# amplifier4c.net
KiCad netlist of a schematic drawn in EAGLE
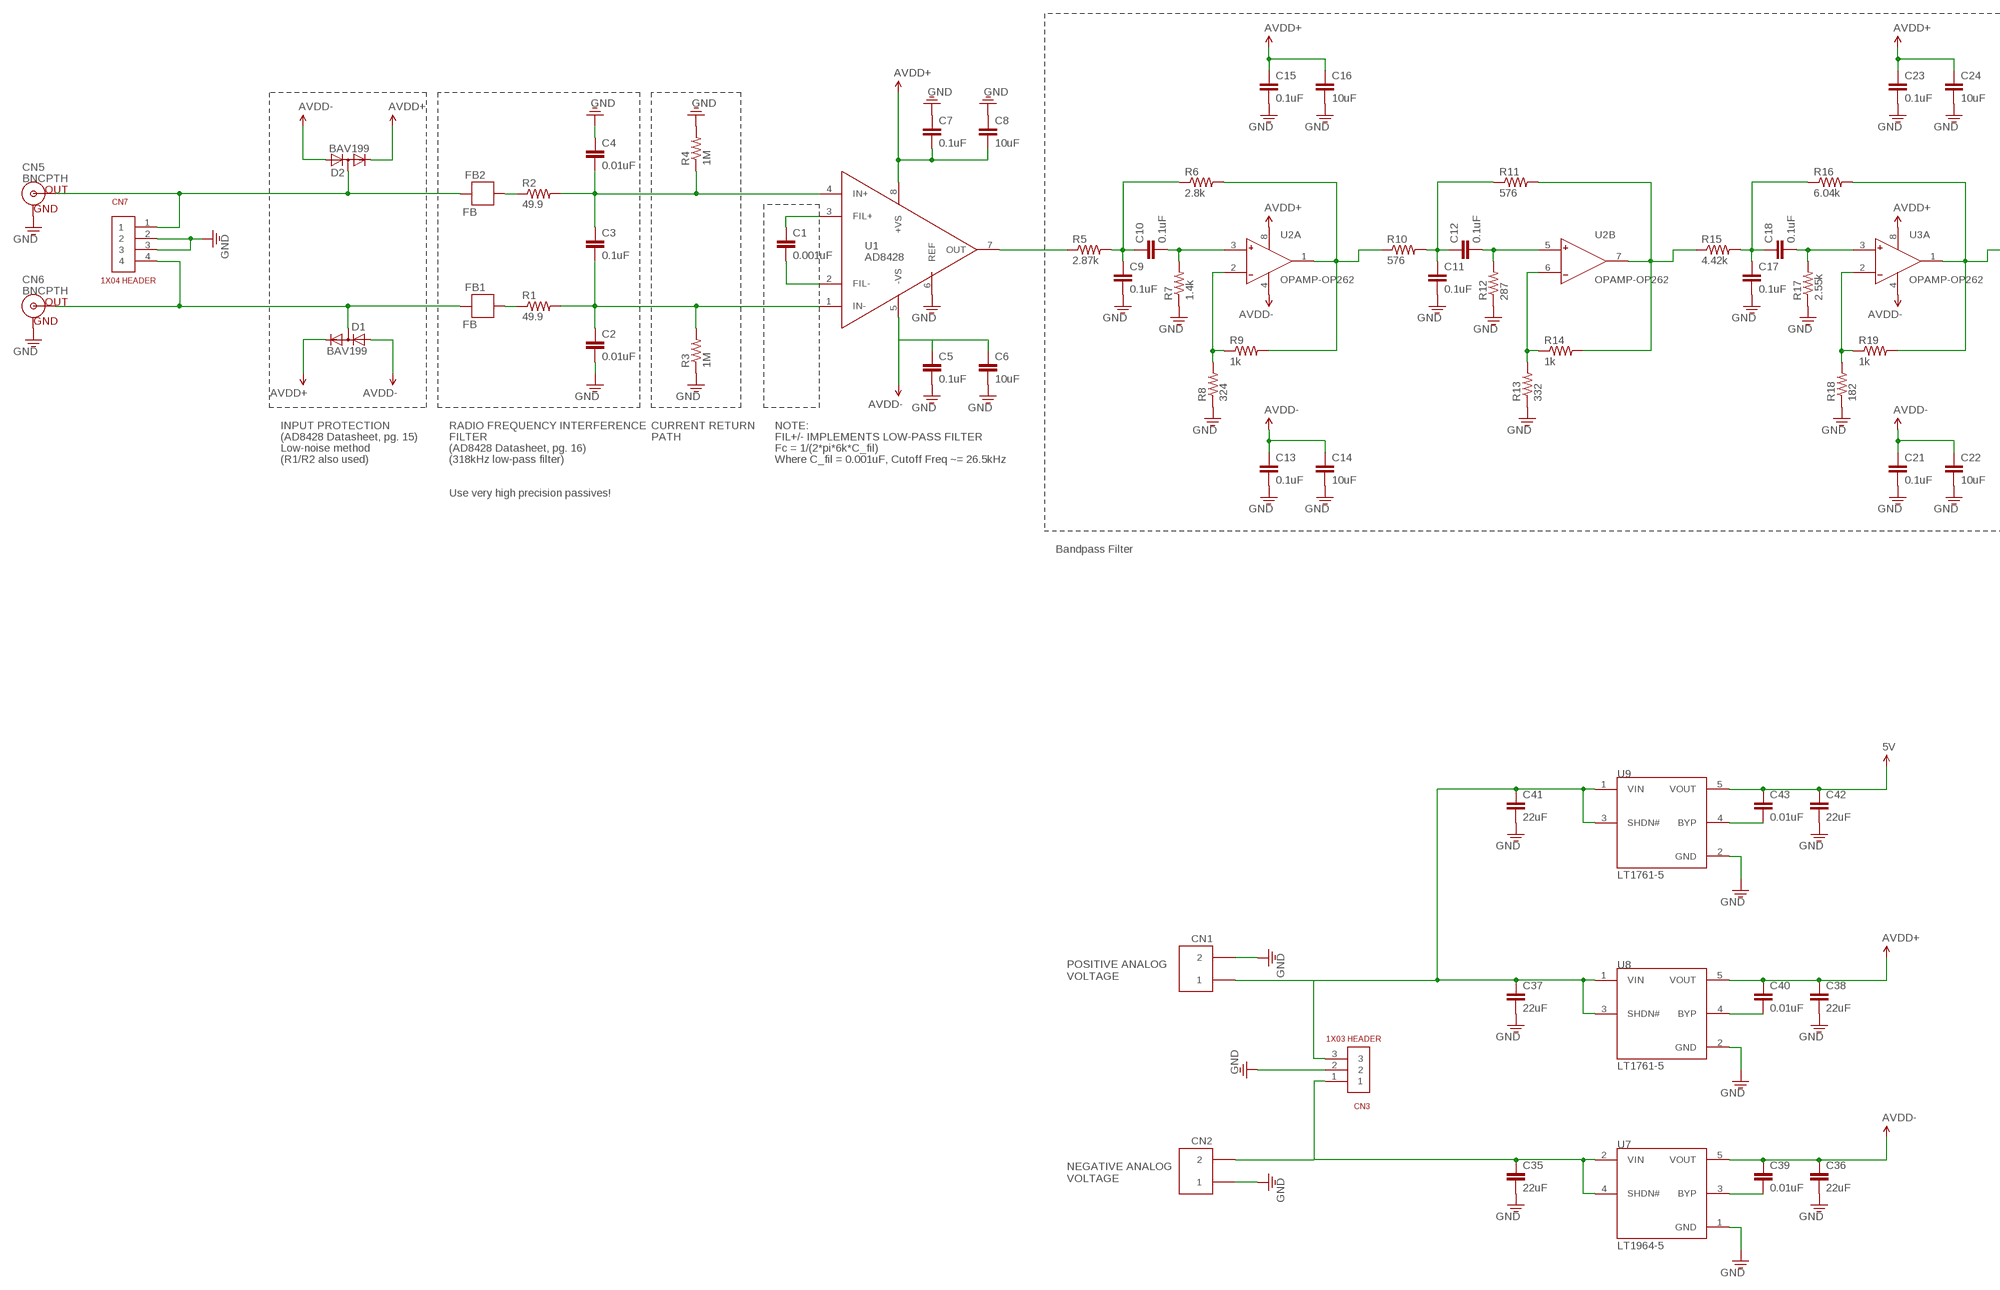
[diagram p0: schematic, sheet 1, part 1 of 2]
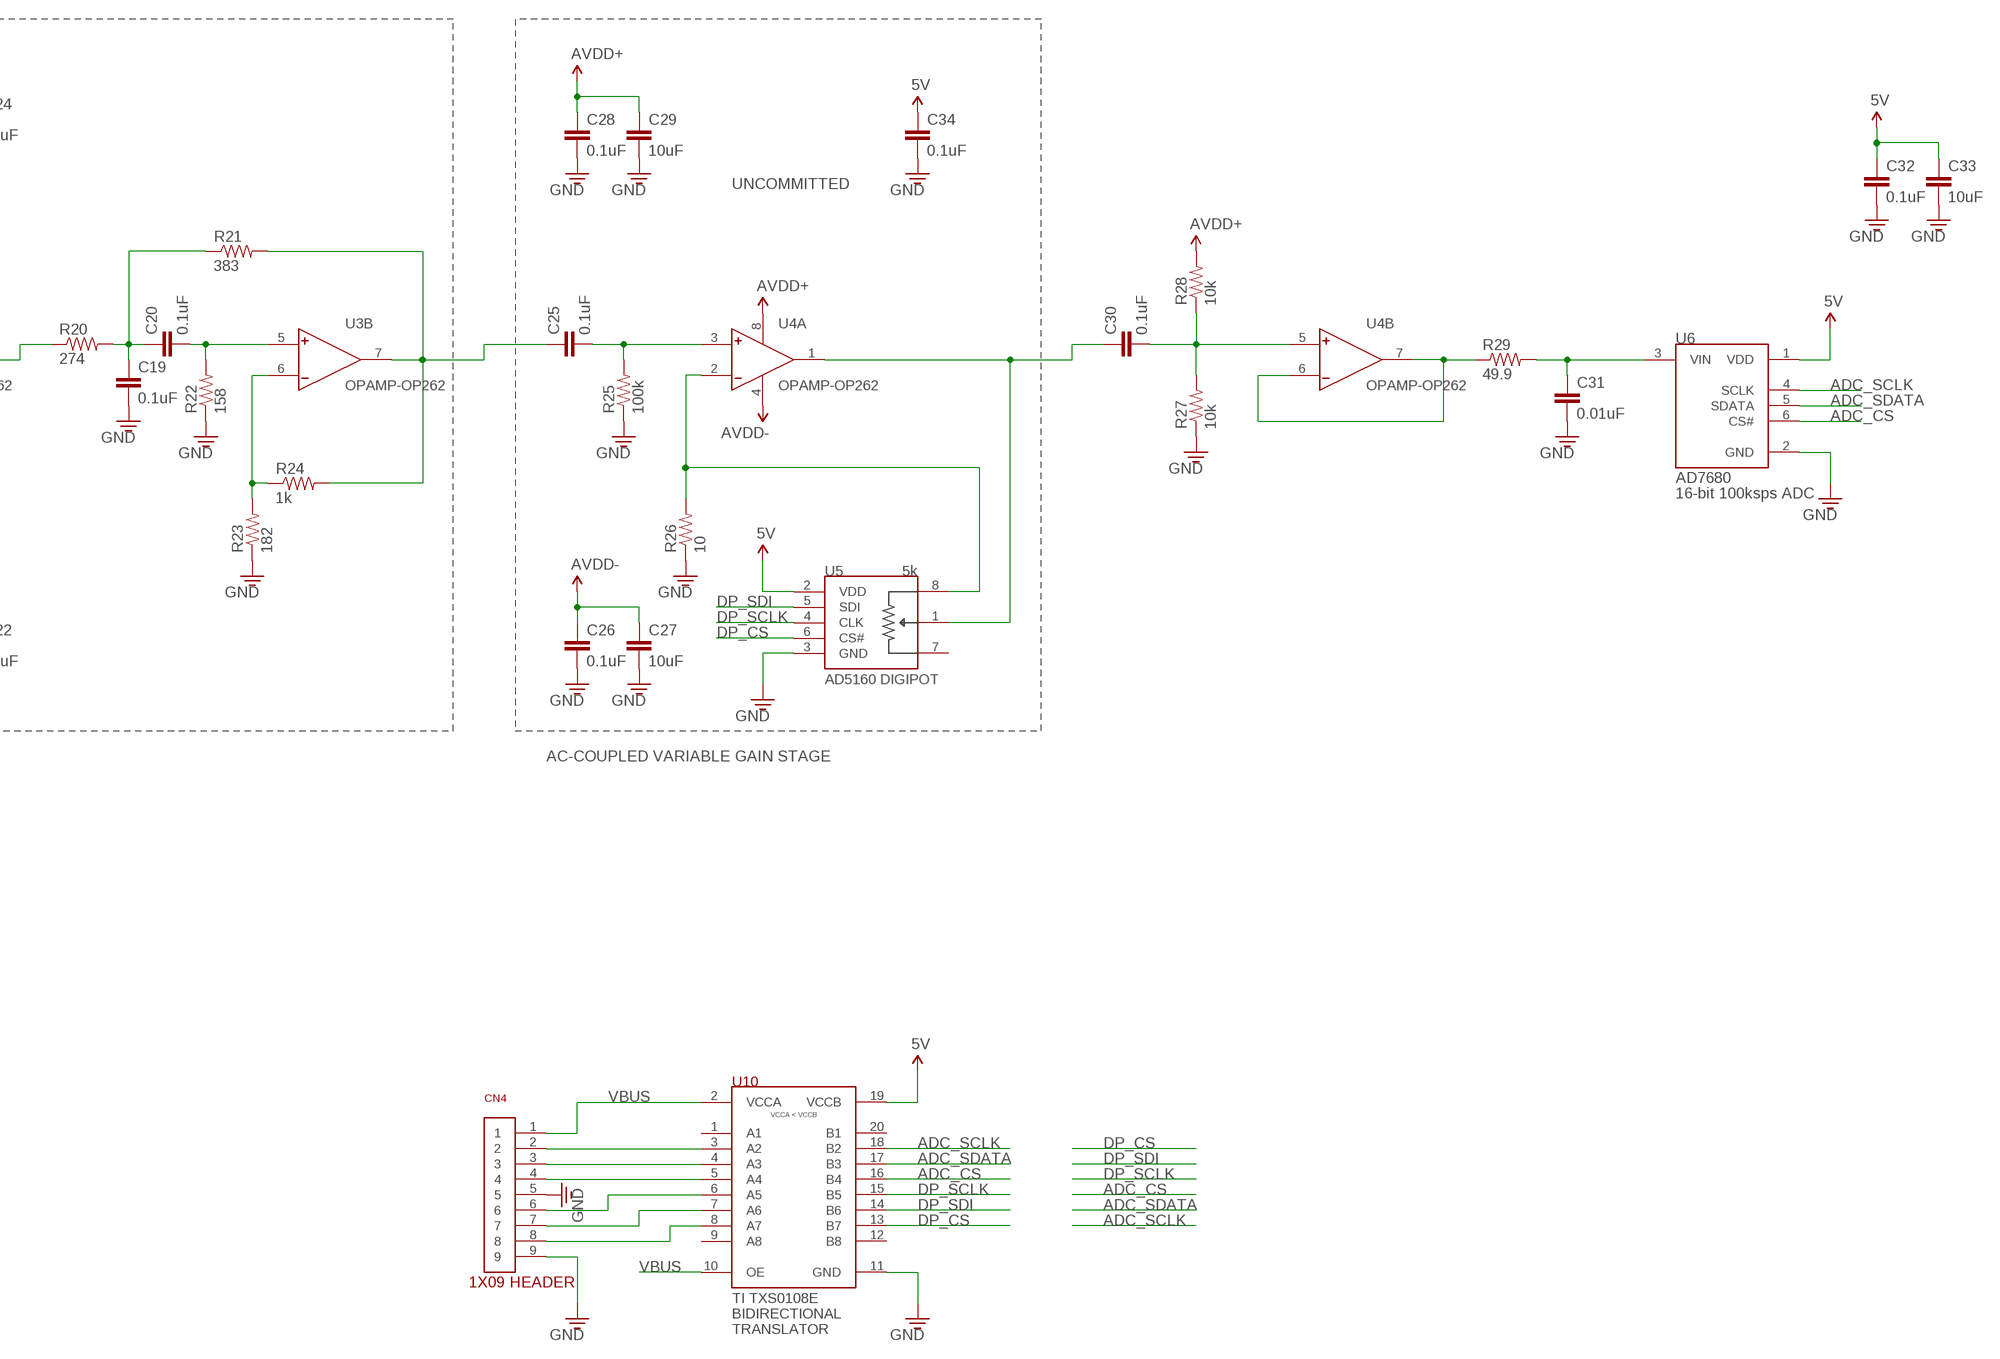
[diagram p1: schematic, sheet 1, part 2 of 2]

(export (version "E")
  (design (tool "Eeschema 10.0.6"))
  (components
    (comp (ref "C1")
      (value "0.001uF")
      (footprint "eagle-import:0603")
      (libsource (lib "eagle-import") (part "CAP0603"))
    )
    (comp (ref "C2")
      (value "0.01uF")
      (footprint "eagle-import:0603")
      (libsource (lib "eagle-import") (part "CAP0603"))
    )
    (comp (ref "C3")
      (value "0.1uF")
      (footprint "eagle-import:0603")
      (libsource (lib "eagle-import") (part "CAP0603"))
    )
    (comp (ref "C4")
      (value "0.01uF")
      (footprint "eagle-import:0603")
      (libsource (lib "eagle-import") (part "CAP0603"))
    )
    (comp (ref "C5")
      (value "0.1uF")
      (footprint "eagle-import:0603")
      (libsource (lib "eagle-import") (part "CAP0603"))
    )
    (comp (ref "C6")
      (value "10uF")
      (footprint "eagle-import:0805")
      (libsource (lib "eagle-import") (part "lowfieldmri_CAP0805"))
    )
    (comp (ref "C7")
      (value "0.1uF")
      (footprint "eagle-import:0603")
      (libsource (lib "eagle-import") (part "CAP0603"))
    )
    (comp (ref "C8")
      (value "10uF")
      (footprint "eagle-import:0805")
      (libsource (lib "eagle-import") (part "lowfieldmri_CAP0805"))
    )
    (comp (ref "C9")
      (value "0.1uF")
      (footprint "eagle-import:0603")
      (libsource (lib "eagle-import") (part "CAP0603"))
    )
    (comp (ref "C10")
      (value "0.1uF")
      (footprint "eagle-import:0603")
      (libsource (lib "eagle-import") (part "CAP0603"))
    )
    (comp (ref "C11")
      (value "0.1uF")
      (footprint "eagle-import:0603")
      (libsource (lib "eagle-import") (part "CAP0603"))
    )
    (comp (ref "C12")
      (value "0.1uF")
      (footprint "eagle-import:0603")
      (libsource (lib "eagle-import") (part "CAP0603"))
    )
    (comp (ref "C13")
      (value "0.1uF")
      (footprint "eagle-import:0603")
      (libsource (lib "eagle-import") (part "CAP0603"))
    )
    (comp (ref "C14")
      (value "10uF")
      (footprint "eagle-import:0805")
      (libsource (lib "eagle-import") (part "lowfieldmri_CAP0805"))
    )
    (comp (ref "C15")
      (value "0.1uF")
      (footprint "eagle-import:0603")
      (libsource (lib "eagle-import") (part "CAP0603"))
    )
    (comp (ref "C16")
      (value "10uF")
      (footprint "eagle-import:0805")
      (libsource (lib "eagle-import") (part "lowfieldmri_CAP0805"))
    )
    (comp (ref "C17")
      (value "0.1uF")
      (footprint "eagle-import:0603")
      (libsource (lib "eagle-import") (part "CAP0603"))
    )
    (comp (ref "C18")
      (value "0.1uF")
      (footprint "eagle-import:0603")
      (libsource (lib "eagle-import") (part "CAP0603"))
    )
    (comp (ref "C19")
      (value "0.1uF")
      (footprint "eagle-import:0603")
      (libsource (lib "eagle-import") (part "CAP0603"))
    )
    (comp (ref "C20")
      (value "0.1uF")
      (footprint "eagle-import:0603")
      (libsource (lib "eagle-import") (part "CAP0603"))
    )
    (comp (ref "C21")
      (value "0.1uF")
      (footprint "eagle-import:0603")
      (libsource (lib "eagle-import") (part "CAP0603"))
    )
    (comp (ref "C22")
      (value "10uF")
      (footprint "eagle-import:0805")
      (libsource (lib "eagle-import") (part "lowfieldmri_CAP0805"))
    )
    (comp (ref "C23")
      (value "0.1uF")
      (footprint "eagle-import:0603")
      (libsource (lib "eagle-import") (part "CAP0603"))
    )
    (comp (ref "C24")
      (value "10uF")
      (footprint "eagle-import:0805")
      (libsource (lib "eagle-import") (part "lowfieldmri_CAP0805"))
    )
    (comp (ref "C25")
      (value "0.1uF")
      (footprint "eagle-import:0603")
      (libsource (lib "eagle-import") (part "CAP0603"))
    )
    (comp (ref "C26")
      (value "0.1uF")
      (footprint "eagle-import:0603")
      (libsource (lib "eagle-import") (part "CAP0603"))
    )
    (comp (ref "C27")
      (value "10uF")
      (footprint "eagle-import:0805")
      (libsource (lib "eagle-import") (part "lowfieldmri_CAP0805"))
    )
    (comp (ref "C28")
      (value "0.1uF")
      (footprint "eagle-import:0603")
      (libsource (lib "eagle-import") (part "CAP0603"))
    )
    (comp (ref "C29")
      (value "10uF")
      (footprint "eagle-import:0805")
      (libsource (lib "eagle-import") (part "lowfieldmri_CAP0805"))
    )
    (comp (ref "C30")
      (value "0.1uF")
      (footprint "eagle-import:0603")
      (libsource (lib "eagle-import") (part "CAP0603"))
    )
    (comp (ref "C31")
      (value "0.01uF")
      (footprint "eagle-import:0603")
      (libsource (lib "eagle-import") (part "CAP0603"))
    )
    (comp (ref "C32")
      (value "0.1uF")
      (footprint "eagle-import:0603")
      (libsource (lib "eagle-import") (part "CAP0603"))
    )
    (comp (ref "C33")
      (value "10uF")
      (footprint "eagle-import:0805")
      (libsource (lib "eagle-import") (part "lowfieldmri_CAP0805"))
    )
    (comp (ref "C34")
      (value "0.1uF")
      (footprint "eagle-import:0603")
      (libsource (lib "eagle-import") (part "CAP0603"))
    )
    (comp (ref "C35")
      (value "22uF")
      (footprint "eagle-import:1206")
      (libsource (lib "eagle-import") (part "CAP1206"))
    )
    (comp (ref "C36")
      (value "22uF")
      (footprint "eagle-import:1206")
      (libsource (lib "eagle-import") (part "CAP1206"))
    )
    (comp (ref "C37")
      (value "22uF")
      (footprint "eagle-import:1206")
      (libsource (lib "eagle-import") (part "CAP1206"))
    )
    (comp (ref "C38")
      (value "22uF")
      (footprint "eagle-import:1206")
      (libsource (lib "eagle-import") (part "CAP1206"))
    )
    (comp (ref "C39")
      (value "0.01uF")
      (footprint "eagle-import:0603")
      (libsource (lib "eagle-import") (part "CAP0603"))
    )
    (comp (ref "C40")
      (value "0.01uF")
      (footprint "eagle-import:0603")
      (libsource (lib "eagle-import") (part "CAP0603"))
    )
    (comp (ref "C41")
      (value "22uF")
      (footprint "eagle-import:1206")
      (libsource (lib "eagle-import") (part "CAP1206"))
    )
    (comp (ref "C42")
      (value "22uF")
      (footprint "eagle-import:1206")
      (libsource (lib "eagle-import") (part "CAP1206"))
    )
    (comp (ref "C43")
      (value "0.01uF")
      (footprint "eagle-import:0603")
      (libsource (lib "eagle-import") (part "CAP0603"))
    )
    (comp (ref "CN1")
      (value "SCREWTERMINAL-2PIN")
      (footprint "eagle-import:SCREWTERMINAL-2PIN")
      (libsource (lib "eagle-import") (part "SCREWTERMINAL-2PIN"))
    )
    (comp (ref "CN2")
      (value "SCREWTERMINAL-2PIN")
      (footprint "eagle-import:SCREWTERMINAL-2PIN")
      (libsource (lib "eagle-import") (part "SCREWTERMINAL-2PIN"))
    )
    (comp (ref "CN3")
      (value "1X03")
      (footprint "eagle-import:1X03")
      (libsource (lib "eagle-import") (part "1X03"))
    )
    (comp (ref "CN4")
      (value "1X09")
      (footprint "eagle-import:1X09")
      (libsource (lib "eagle-import") (part "1X09"))
    )
    (comp (ref "CN5")
      (value "BNCPTH")
      (footprint "eagle-import:BNC")
      (libsource (lib "eagle-import") (part "BNCPTH"))
    )
    (comp (ref "CN6")
      (value "BNCPTH")
      (footprint "eagle-import:BNC")
      (libsource (lib "eagle-import") (part "BNCPTH"))
    )
    (comp (ref "CN7")
      (value "1X04")
      (footprint "eagle-import:1X04")
      (libsource (lib "eagle-import") (part "1X04"))
    )
    (comp (ref "D1")
      (value "BAV199")
      (footprint "eagle-import:SOT23")
      (libsource (lib "eagle-import") (part "BAV199"))
    )
    (comp (ref "D2")
      (value "BAV199")
      (footprint "eagle-import:SOT23")
      (libsource (lib "eagle-import") (part "BAV199"))
    )
    (comp (ref "FB1")
      (value "FB")
      (footprint "eagle-import:0603")
      (libsource (lib "eagle-import") (part "FB"))
    )
    (comp (ref "FB2")
      (value "FB")
      (footprint "eagle-import:0603")
      (libsource (lib "eagle-import") (part "FB"))
    )
    (comp (ref "R1")
      (value "49.9")
      (footprint "eagle-import:0603")
      (libsource (lib "eagle-import") (part "RESISTOR0603"))
    )
    (comp (ref "R2")
      (value "49.9")
      (footprint "eagle-import:0603")
      (libsource (lib "eagle-import") (part "RESISTOR0603"))
    )
    (comp (ref "R3")
      (value "1M")
      (footprint "eagle-import:0603")
      (libsource (lib "eagle-import") (part "RESISTOR0603"))
    )
    (comp (ref "R4")
      (value "1M")
      (footprint "eagle-import:0603")
      (libsource (lib "eagle-import") (part "RESISTOR0603"))
    )
    (comp (ref "R5")
      (value "2.87k")
      (footprint "eagle-import:0603")
      (libsource (lib "eagle-import") (part "RESISTOR0603"))
    )
    (comp (ref "R6")
      (value "2.8k")
      (footprint "eagle-import:0603")
      (libsource (lib "eagle-import") (part "RESISTOR0603"))
    )
    (comp (ref "R7")
      (value "1.4k")
      (footprint "eagle-import:0603")
      (libsource (lib "eagle-import") (part "RESISTOR0603"))
    )
    (comp (ref "R8")
      (value "324")
      (footprint "eagle-import:0603")
      (libsource (lib "eagle-import") (part "RESISTOR0603"))
    )
    (comp (ref "R9")
      (value "1k")
      (footprint "eagle-import:0603")
      (libsource (lib "eagle-import") (part "RESISTOR0603"))
    )
    (comp (ref "R10")
      (value "576")
      (footprint "eagle-import:0603")
      (libsource (lib "eagle-import") (part "RESISTOR0603"))
    )
    (comp (ref "R11")
      (value "576")
      (footprint "eagle-import:0603")
      (libsource (lib "eagle-import") (part "RESISTOR0603"))
    )
    (comp (ref "R12")
      (value "287")
      (footprint "eagle-import:0603")
      (libsource (lib "eagle-import") (part "RESISTOR0603"))
    )
    (comp (ref "R13")
      (value "332")
      (footprint "eagle-import:0603")
      (libsource (lib "eagle-import") (part "RESISTOR0603"))
    )
    (comp (ref "R14")
      (value "1k")
      (footprint "eagle-import:0603")
      (libsource (lib "eagle-import") (part "RESISTOR0603"))
    )
    (comp (ref "R15")
      (value "4.42k")
      (footprint "eagle-import:0603")
      (libsource (lib "eagle-import") (part "RESISTOR0603"))
    )
    (comp (ref "R16")
      (value "6.04k")
      (footprint "eagle-import:0603")
      (libsource (lib "eagle-import") (part "RESISTOR0603"))
    )
    (comp (ref "R17")
      (value "2.55k")
      (footprint "eagle-import:0603")
      (libsource (lib "eagle-import") (part "RESISTOR0603"))
    )
    (comp (ref "R18")
      (value "182")
      (footprint "eagle-import:0603")
      (libsource (lib "eagle-import") (part "RESISTOR0603"))
    )
    (comp (ref "R19")
      (value "1k")
      (footprint "eagle-import:0603")
      (libsource (lib "eagle-import") (part "RESISTOR0603"))
    )
    (comp (ref "R20")
      (value "274")
      (footprint "eagle-import:0603")
      (libsource (lib "eagle-import") (part "RESISTOR0603"))
    )
    (comp (ref "R21")
      (value "383")
      (footprint "eagle-import:0603")
      (libsource (lib "eagle-import") (part "RESISTOR0603"))
    )
    (comp (ref "R22")
      (value "158")
      (footprint "eagle-import:0603")
      (libsource (lib "eagle-import") (part "RESISTOR0603"))
    )
    (comp (ref "R23")
      (value "182")
      (footprint "eagle-import:0603")
      (libsource (lib "eagle-import") (part "RESISTOR0603"))
    )
    (comp (ref "R24")
      (value "1k")
      (footprint "eagle-import:0603")
      (libsource (lib "eagle-import") (part "RESISTOR0603"))
    )
    (comp (ref "R25")
      (value "100k")
      (footprint "eagle-import:0603")
      (libsource (lib "eagle-import") (part "RESISTOR0603"))
    )
    (comp (ref "R26")
      (value "10")
      (footprint "eagle-import:0603")
      (libsource (lib "eagle-import") (part "RESISTOR0603"))
    )
    (comp (ref "R27")
      (value "10k")
      (footprint "eagle-import:0603")
      (libsource (lib "eagle-import") (part "RESISTOR0603"))
    )
    (comp (ref "R28")
      (value "10k")
      (footprint "eagle-import:0603")
      (libsource (lib "eagle-import") (part "RESISTOR0603"))
    )
    (comp (ref "R29")
      (value "49.9")
      (footprint "eagle-import:0603")
      (libsource (lib "eagle-import") (part "RESISTOR0603"))
    )
    (comp (ref "U1")
      (value "OPAMP-AD8428")
      (footprint "eagle-import:SOIC-8")
      (libsource (lib "eagle-import") (part "OPAMP-AD8428"))
    )
    (comp (ref "U2")
      (value "OPAMP-OP262")
      (footprint "eagle-import:SOIC-8")
      (libsource (lib "eagle-import") (part "OPAMP-OP262"))
    )
    (comp (ref "U3")
      (value "OPAMP-OP262")
      (footprint "eagle-import:SOIC-8")
      (libsource (lib "eagle-import") (part "OPAMP-OP262"))
    )
    (comp (ref "U4")
      (value "OPAMP-OP262")
      (footprint "eagle-import:SOIC-8")
      (libsource (lib "eagle-import") (part "OPAMP-OP262"))
    )
    (comp (ref "U5")
      (value "5k")
      (footprint "eagle-import:SOT-23-8")
      (libsource (lib "eagle-import") (part "AD5160"))
    )
    (comp (ref "U6")
      (value "ADC-AD7680")
      (footprint "eagle-import:SOT-23-6L")
      (libsource (lib "eagle-import") (part "ADC-AD7680"))
    )
    (comp (ref "U7")
      (value "LT1964-5")
      (footprint "eagle-import:SOT-23-5L")
      (libsource (lib "eagle-import") (part "REG-LT1964-X"))
    )
    (comp (ref "U8")
      (value "LT1761-5")
      (footprint "eagle-import:SOT-23-5L")
      (libsource (lib "eagle-import") (part "REG-LT1761-X"))
    )
    (comp (ref "U9")
      (value "LT1761-5")
      (footprint "eagle-import:SOT-23-5L")
      (libsource (lib "eagle-import") (part "REG-LT1761-X"))
    )
    (comp (ref "U10")
      (value "TRANSLATOR-TXS0108E")
      (footprint "eagle-import:TSSOP-20")
      (libsource (lib "eagle-import") (part "TRANSLATOR-TXS0108E"))
    )
  )
  (nets
    (net (code "1") (name "/ADC_CS") (class "Default")
      (node (ref "U10") (pin "16") (pinfunction "B4_16") (pintype "bidirectional"))
      (node (ref "U6") (pin "6") (pinfunction "CS#_6") (pintype "bidirectional"))
    )
    (net (code "2") (name "/ADC_SCLK") (class "Default")
      (node (ref "U10") (pin "18") (pinfunction "B2_18") (pintype "bidirectional"))
      (node (ref "U6") (pin "4") (pinfunction "SCLK_4") (pintype "bidirectional"))
    )
    (net (code "3") (name "/ADC_SDATA") (class "Default")
      (node (ref "U10") (pin "17") (pinfunction "B3_17") (pintype "bidirectional"))
      (node (ref "U6") (pin "5") (pinfunction "SDATA_5") (pintype "bidirectional"))
    )
    (net (code "4") (name "/DP_CS") (class "Default")
      (node (ref "U10") (pin "13") (pinfunction "B7_13") (pintype "bidirectional"))
      (node (ref "U5") (pin "6") (pinfunction "CS#_6") (pintype "bidirectional"))
    )
    (net (code "5") (name "/DP_SCLK") (class "Default")
      (node (ref "U10") (pin "15") (pinfunction "B5_15") (pintype "bidirectional"))
      (node (ref "U5") (pin "4") (pinfunction "CLK_4") (pintype "bidirectional"))
    )
    (net (code "6") (name "/DP_SDI") (class "Default")
      (node (ref "U10") (pin "14") (pinfunction "B6_14") (pintype "bidirectional"))
      (node (ref "U5") (pin "5") (pinfunction "SDI_5") (pintype "bidirectional"))
    )
    (net (code "7") (name "/VBUS") (class "Default")
      (node (ref "CN4") (pin "1") (pinfunction "1_1") (pintype "bidirectional"))
      (node (ref "U10") (pin "10") (pinfunction "OE_10") (pintype "bidirectional"))
      (node (ref "U10") (pin "2") (pinfunction "VCCA_2") (pintype "bidirectional"))
    )
    (net (code "8") (name "5V") (class "Default")
      (node (ref "C32") (pin "1") (pinfunction "1_1") (pintype "passive"))
      (node (ref "C33") (pin "1") (pinfunction "1_1") (pintype "passive"))
      (node (ref "C34") (pin "1") (pinfunction "1_1") (pintype "passive"))
      (node (ref "C42") (pin "1") (pinfunction "1_1") (pintype "passive"))
      (node (ref "C43") (pin "1") (pinfunction "1_1") (pintype "passive"))
      (node (ref "U10") (pin "19") (pinfunction "VCCB_19") (pintype "bidirectional"))
      (node (ref "U5") (pin "2") (pinfunction "VDD_2") (pintype "bidirectional"))
      (node (ref "U6") (pin "1") (pinfunction "VDD_1") (pintype "bidirectional"))
      (node (ref "U9") (pin "5") (pinfunction "VOUT_5") (pintype "bidirectional"))
    )
    (net (code "9") (name "AVDD+") (class "Default")
      (node (ref "C15") (pin "1") (pinfunction "1_1") (pintype "passive"))
      (node (ref "C16") (pin "1") (pinfunction "1_1") (pintype "passive"))
      (node (ref "C23") (pin "1") (pinfunction "1_1") (pintype "passive"))
      (node (ref "C24") (pin "1") (pinfunction "1_1") (pintype "passive"))
      (node (ref "C28") (pin "1") (pinfunction "1_1") (pintype "passive"))
      (node (ref "C29") (pin "1") (pinfunction "1_1") (pintype "passive"))
      (node (ref "C38") (pin "1") (pinfunction "1_1") (pintype "passive"))
      (node (ref "C40") (pin "1") (pinfunction "1_1") (pintype "passive"))
      (node (ref "C7") (pin "2") (pinfunction "2_2") (pintype "passive"))
      (node (ref "C8") (pin "2") (pinfunction "2_2") (pintype "passive"))
      (node (ref "D1") (pin "2") (pinfunction "C_2") (pintype "passive"))
      (node (ref "D2") (pin "2") (pinfunction "C_2") (pintype "passive"))
      (node (ref "R28") (pin "2") (pinfunction "2_2") (pintype "passive"))
      (node (ref "U1") (pin "8") (pinfunction "+VS_8") (pintype "bidirectional"))
      (node (ref "U2") (pin "8") (pinfunction "V+_8") (pintype "bidirectional"))
      (node (ref "U3") (pin "8") (pinfunction "V+_8") (pintype "bidirectional"))
      (node (ref "U4") (pin "8") (pinfunction "V+_8") (pintype "bidirectional"))
      (node (ref "U8") (pin "5") (pinfunction "VOUT_5") (pintype "bidirectional"))
    )
    (net (code "10") (name "AVDD-") (class "Default")
      (node (ref "C13") (pin "1") (pinfunction "1_1") (pintype "passive"))
      (node (ref "C14") (pin "1") (pinfunction "1_1") (pintype "passive"))
      (node (ref "C21") (pin "1") (pinfunction "1_1") (pintype "passive"))
      (node (ref "C22") (pin "1") (pinfunction "1_1") (pintype "passive"))
      (node (ref "C26") (pin "1") (pinfunction "1_1") (pintype "passive"))
      (node (ref "C27") (pin "1") (pinfunction "1_1") (pintype "passive"))
      (node (ref "C36") (pin "1") (pinfunction "1_1") (pintype "passive"))
      (node (ref "C39") (pin "1") (pinfunction "1_1") (pintype "passive"))
      (node (ref "C5") (pin "1") (pinfunction "1_1") (pintype "passive"))
      (node (ref "C6") (pin "1") (pinfunction "1_1") (pintype "passive"))
      (node (ref "D1") (pin "1") (pinfunction "A_1") (pintype "passive"))
      (node (ref "D2") (pin "1") (pinfunction "A_1") (pintype "passive"))
      (node (ref "U1") (pin "5") (pinfunction "-VS_5") (pintype "bidirectional"))
      (node (ref "U2") (pin "4") (pinfunction "V-_4") (pintype "bidirectional"))
      (node (ref "U3") (pin "4") (pinfunction "V-_4") (pintype "bidirectional"))
      (node (ref "U4") (pin "4") (pinfunction "V-_4") (pintype "bidirectional"))
      (node (ref "U7") (pin "5") (pinfunction "VOUT_5") (pintype "bidirectional"))
    )
    (net (code "11") (name "GND") (class "Default")
      (node (ref "C11") (pin "2") (pinfunction "2_2") (pintype "passive"))
      (node (ref "C13") (pin "2") (pinfunction "2_2") (pintype "passive"))
      (node (ref "C14") (pin "2") (pinfunction "2_2") (pintype "passive"))
      (node (ref "C15") (pin "2") (pinfunction "2_2") (pintype "passive"))
      (node (ref "C16") (pin "2") (pinfunction "2_2") (pintype "passive"))
      (node (ref "C17") (pin "2") (pinfunction "2_2") (pintype "passive"))
      (node (ref "C19") (pin "2") (pinfunction "2_2") (pintype "passive"))
      (node (ref "C2") (pin "2") (pinfunction "2_2") (pintype "passive"))
      (node (ref "C21") (pin "2") (pinfunction "2_2") (pintype "passive"))
      (node (ref "C22") (pin "2") (pinfunction "2_2") (pintype "passive"))
      (node (ref "C23") (pin "2") (pinfunction "2_2") (pintype "passive"))
      (node (ref "C24") (pin "2") (pinfunction "2_2") (pintype "passive"))
      (node (ref "C26") (pin "2") (pinfunction "2_2") (pintype "passive"))
      (node (ref "C27") (pin "2") (pinfunction "2_2") (pintype "passive"))
      (node (ref "C28") (pin "2") (pinfunction "2_2") (pintype "passive"))
      (node (ref "C29") (pin "2") (pinfunction "2_2") (pintype "passive"))
      (node (ref "C31") (pin "2") (pinfunction "2_2") (pintype "passive"))
      (node (ref "C32") (pin "2") (pinfunction "2_2") (pintype "passive"))
      (node (ref "C33") (pin "2") (pinfunction "2_2") (pintype "passive"))
      (node (ref "C34") (pin "2") (pinfunction "2_2") (pintype "passive"))
      (node (ref "C35") (pin "2") (pinfunction "2_2") (pintype "passive"))
      (node (ref "C36") (pin "2") (pinfunction "2_2") (pintype "passive"))
      (node (ref "C37") (pin "2") (pinfunction "2_2") (pintype "passive"))
      (node (ref "C38") (pin "2") (pinfunction "2_2") (pintype "passive"))
      (node (ref "C4") (pin "1") (pinfunction "1_1") (pintype "passive"))
      (node (ref "C41") (pin "2") (pinfunction "2_2") (pintype "passive"))
      (node (ref "C42") (pin "2") (pinfunction "2_2") (pintype "passive"))
      (node (ref "C5") (pin "2") (pinfunction "2_2") (pintype "passive"))
      (node (ref "C6") (pin "2") (pinfunction "2_2") (pintype "passive"))
      (node (ref "C7") (pin "1") (pinfunction "1_1") (pintype "passive"))
      (node (ref "C8") (pin "1") (pinfunction "1_1") (pintype "passive"))
      (node (ref "C9") (pin "2") (pinfunction "2_2") (pintype "passive"))
      (node (ref "CN1") (pin "2") (pinfunction "2_2") (pintype "bidirectional"))
      (node (ref "CN2") (pin "1") (pinfunction "1_1") (pintype "bidirectional"))
      (node (ref "CN3") (pin "2") (pinfunction "2_2") (pintype "bidirectional"))
      (node (ref "CN4") (pin "5") (pinfunction "5_5") (pintype "bidirectional"))
      (node (ref "CN4") (pin "9") (pinfunction "9_9") (pintype "bidirectional"))
      (node (ref "CN5") (pin "GND") (pinfunction "GND_GND") (pintype "bidirectional"))
      (node (ref "CN6") (pin "GND") (pinfunction "GND_GND") (pintype "bidirectional"))
      (node (ref "CN7") (pin "2") (pinfunction "2_2") (pintype "bidirectional"))
      (node (ref "CN7") (pin "3") (pinfunction "3_3") (pintype "bidirectional"))
      (node (ref "R12") (pin "1") (pinfunction "1_1") (pintype "passive"))
      (node (ref "R13") (pin "1") (pinfunction "1_1") (pintype "passive"))
      (node (ref "R17") (pin "1") (pinfunction "1_1") (pintype "passive"))
      (node (ref "R18") (pin "1") (pinfunction "1_1") (pintype "passive"))
      (node (ref "R22") (pin "1") (pinfunction "1_1") (pintype "passive"))
      (node (ref "R23") (pin "1") (pinfunction "1_1") (pintype "passive"))
      (node (ref "R25") (pin "1") (pinfunction "1_1") (pintype "passive"))
      (node (ref "R26") (pin "1") (pinfunction "1_1") (pintype "passive"))
      (node (ref "R27") (pin "1") (pinfunction "1_1") (pintype "passive"))
      (node (ref "R3") (pin "1") (pinfunction "1_1") (pintype "passive"))
      (node (ref "R4") (pin "2") (pinfunction "2_2") (pintype "passive"))
      (node (ref "R7") (pin "1") (pinfunction "1_1") (pintype "passive"))
      (node (ref "R8") (pin "1") (pinfunction "1_1") (pintype "passive"))
      (node (ref "U1") (pin "6") (pinfunction "REF_6") (pintype "bidirectional"))
      (node (ref "U10") (pin "11") (pinfunction "GND_11") (pintype "bidirectional"))
      (node (ref "U5") (pin "3") (pinfunction "GND_3") (pintype "bidirectional"))
      (node (ref "U6") (pin "2") (pinfunction "GND_2") (pintype "bidirectional"))
      (node (ref "U7") (pin "1") (pinfunction "GND_1") (pintype "bidirectional"))
      (node (ref "U8") (pin "2") (pinfunction "GND_2") (pintype "bidirectional"))
      (node (ref "U9") (pin "2") (pinfunction "GND_2") (pintype "bidirectional"))
    )
    (net (code "12") (name "Net-(C10-Pad1)") (class "Default")
      (node (ref "C10") (pin "1") (pinfunction "1_1") (pintype "passive"))
      (node (ref "C9") (pin "1") (pinfunction "1_1") (pintype "passive"))
      (node (ref "R5") (pin "2") (pinfunction "2_2") (pintype "passive"))
      (node (ref "R6") (pin "1") (pinfunction "1_1") (pintype "passive"))
    )
    (net (code "13") (name "Net-(C11-Pad1)") (class "Default")
      (node (ref "C11") (pin "1") (pinfunction "1_1") (pintype "passive"))
      (node (ref "C12") (pin "1") (pinfunction "1_1") (pintype "passive"))
      (node (ref "R10") (pin "2") (pinfunction "2_2") (pintype "passive"))
      (node (ref "R11") (pin "1") (pinfunction "1_1") (pintype "passive"))
    )
    (net (code "14") (name "Net-(C17-Pad1)") (class "Default")
      (node (ref "C17") (pin "1") (pinfunction "1_1") (pintype "passive"))
      (node (ref "C18") (pin "1") (pinfunction "1_1") (pintype "passive"))
      (node (ref "R15") (pin "2") (pinfunction "2_2") (pintype "passive"))
      (node (ref "R16") (pin "1") (pinfunction "1_1") (pintype "passive"))
    )
    (net (code "15") (name "Net-(C19-Pad1)") (class "Default")
      (node (ref "C19") (pin "1") (pinfunction "1_1") (pintype "passive"))
      (node (ref "C20") (pin "1") (pinfunction "1_1") (pintype "passive"))
      (node (ref "R20") (pin "2") (pinfunction "2_2") (pintype "passive"))
      (node (ref "R21") (pin "1") (pinfunction "1_1") (pintype "passive"))
    )
    (net (code "16") (name "Net-(CN5-OUT)") (class "Default")
      (node (ref "CN5") (pin "S") (pinfunction "OUT_S") (pintype "bidirectional"))
      (node (ref "CN7") (pin "1") (pinfunction "1_1") (pintype "bidirectional"))
      (node (ref "D2") (pin "3") (pinfunction "AC_3") (pintype "passive"))
      (node (ref "FB2") (pin "2") (pinfunction "P$2_2") (pintype "bidirectional"))
    )
    (net (code "17") (name "Net-(CN6-OUT)") (class "Default")
      (node (ref "CN6") (pin "S") (pinfunction "OUT_S") (pintype "bidirectional"))
      (node (ref "CN7") (pin "4") (pinfunction "4_4") (pintype "bidirectional"))
      (node (ref "D1") (pin "3") (pinfunction "AC_3") (pintype "passive"))
      (node (ref "FB1") (pin "2") (pinfunction "P$2_2") (pintype "bidirectional"))
    )
    (net (code "18") (name "Net-(FB1-P$1)") (class "Default")
      (node (ref "FB1") (pin "1") (pinfunction "P$1_1") (pintype "bidirectional"))
      (node (ref "R1") (pin "1") (pinfunction "1_1") (pintype "passive"))
    )
    (net (code "19") (name "Net-(FB2-P$1)") (class "Default")
      (node (ref "FB2") (pin "1") (pinfunction "P$1_1") (pintype "bidirectional"))
      (node (ref "R2") (pin "1") (pinfunction "1_1") (pintype "passive"))
    )
    (net (code "20") (name "Net-(U1-FIL+)") (class "Default")
      (node (ref "C1") (pin "1") (pinfunction "1_1") (pintype "passive"))
      (node (ref "U1") (pin "3") (pinfunction "FIL+_3") (pintype "bidirectional"))
    )
    (net (code "21") (name "Net-(U1-FIL-)") (class "Default")
      (node (ref "C1") (pin "2") (pinfunction "2_2") (pintype "passive"))
      (node (ref "U1") (pin "2") (pinfunction "FIL-_2") (pintype "bidirectional"))
    )
    (net (code "22") (name "Net-(U1-IN+)") (class "Default")
      (node (ref "C3") (pin "1") (pinfunction "1_1") (pintype "passive"))
      (node (ref "C4") (pin "2") (pinfunction "2_2") (pintype "passive"))
      (node (ref "R2") (pin "2") (pinfunction "2_2") (pintype "passive"))
      (node (ref "R4") (pin "1") (pinfunction "1_1") (pintype "passive"))
      (node (ref "U1") (pin "4") (pinfunction "IN+_4") (pintype "bidirectional"))
    )
    (net (code "23") (name "Net-(U1-IN-)") (class "Default")
      (node (ref "C2") (pin "1") (pinfunction "1_1") (pintype "passive"))
      (node (ref "C3") (pin "2") (pinfunction "2_2") (pintype "passive"))
      (node (ref "R1") (pin "2") (pinfunction "2_2") (pintype "passive"))
      (node (ref "R3") (pin "2") (pinfunction "2_2") (pintype "passive"))
      (node (ref "U1") (pin "1") (pinfunction "IN-_1") (pintype "bidirectional"))
    )
    (net (code "24") (name "Net-(U1-OUT)") (class "Default")
      (node (ref "R5") (pin "1") (pinfunction "1_1") (pintype "passive"))
      (node (ref "U1") (pin "7") (pinfunction "OUT_7") (pintype "bidirectional"))
    )
    (net (code "25") (name "Net-(U2A-+)") (class "Default")
      (node (ref "C10") (pin "2") (pinfunction "2_2") (pintype "passive"))
      (node (ref "R7") (pin "2") (pinfunction "2_2") (pintype "passive"))
      (node (ref "U2") (pin "3") (pinfunction "+_3") (pintype "bidirectional"))
    )
    (net (code "26") (name "Net-(U2A--)") (class "Default")
      (node (ref "R8") (pin "2") (pinfunction "2_2") (pintype "passive"))
      (node (ref "R9") (pin "1") (pinfunction "1_1") (pintype "passive"))
      (node (ref "U2") (pin "2") (pinfunction "-_2") (pintype "bidirectional"))
    )
    (net (code "27") (name "Net-(U2A-OUT)") (class "Default")
      (node (ref "R10") (pin "1") (pinfunction "1_1") (pintype "passive"))
      (node (ref "R6") (pin "2") (pinfunction "2_2") (pintype "passive"))
      (node (ref "R9") (pin "2") (pinfunction "2_2") (pintype "passive"))
      (node (ref "U2") (pin "1") (pinfunction "OUT_1") (pintype "bidirectional"))
    )
    (net (code "28") (name "Net-(U2B-+)") (class "Default")
      (node (ref "C12") (pin "2") (pinfunction "2_2") (pintype "passive"))
      (node (ref "R12") (pin "2") (pinfunction "2_2") (pintype "passive"))
      (node (ref "U2") (pin "5") (pinfunction "+_5") (pintype "bidirectional"))
    )
    (net (code "29") (name "Net-(U2B--)") (class "Default")
      (node (ref "R13") (pin "2") (pinfunction "2_2") (pintype "passive"))
      (node (ref "R14") (pin "1") (pinfunction "1_1") (pintype "passive"))
      (node (ref "U2") (pin "6") (pinfunction "-_6") (pintype "bidirectional"))
    )
    (net (code "30") (name "Net-(U2B-OUT)") (class "Default")
      (node (ref "R11") (pin "2") (pinfunction "2_2") (pintype "passive"))
      (node (ref "R14") (pin "2") (pinfunction "2_2") (pintype "passive"))
      (node (ref "R15") (pin "1") (pinfunction "1_1") (pintype "passive"))
      (node (ref "U2") (pin "7") (pinfunction "OUT_7") (pintype "bidirectional"))
    )
    (net (code "31") (name "Net-(U3A-+)") (class "Default")
      (node (ref "C18") (pin "2") (pinfunction "2_2") (pintype "passive"))
      (node (ref "R17") (pin "2") (pinfunction "2_2") (pintype "passive"))
      (node (ref "U3") (pin "3") (pinfunction "+_3") (pintype "bidirectional"))
    )
    (net (code "32") (name "Net-(U3A--)") (class "Default")
      (node (ref "R18") (pin "2") (pinfunction "2_2") (pintype "passive"))
      (node (ref "R19") (pin "1") (pinfunction "1_1") (pintype "passive"))
      (node (ref "U3") (pin "2") (pinfunction "-_2") (pintype "bidirectional"))
    )
    (net (code "33") (name "Net-(U3A-OUT)") (class "Default")
      (node (ref "R16") (pin "2") (pinfunction "2_2") (pintype "passive"))
      (node (ref "R19") (pin "2") (pinfunction "2_2") (pintype "passive"))
      (node (ref "R20") (pin "1") (pinfunction "1_1") (pintype "passive"))
      (node (ref "U3") (pin "1") (pinfunction "OUT_1") (pintype "bidirectional"))
    )
    (net (code "34") (name "Net-(U3B-+)") (class "Default")
      (node (ref "C20") (pin "2") (pinfunction "2_2") (pintype "passive"))
      (node (ref "R22") (pin "2") (pinfunction "2_2") (pintype "passive"))
      (node (ref "U3") (pin "5") (pinfunction "+_5") (pintype "bidirectional"))
    )
    (net (code "35") (name "Net-(U3B--)") (class "Default")
      (node (ref "R23") (pin "2") (pinfunction "2_2") (pintype "passive"))
      (node (ref "R24") (pin "1") (pinfunction "1_1") (pintype "passive"))
      (node (ref "U3") (pin "6") (pinfunction "-_6") (pintype "bidirectional"))
    )
    (net (code "36") (name "Net-(U3B-OUT)") (class "Default")
      (node (ref "C25") (pin "1") (pinfunction "1_1") (pintype "passive"))
      (node (ref "R21") (pin "2") (pinfunction "2_2") (pintype "passive"))
      (node (ref "R24") (pin "2") (pinfunction "2_2") (pintype "passive"))
      (node (ref "U3") (pin "7") (pinfunction "OUT_7") (pintype "bidirectional"))
    )
    (net (code "37") (name "Net-(U4A-+)") (class "Default")
      (node (ref "C25") (pin "2") (pinfunction "2_2") (pintype "passive"))
      (node (ref "R25") (pin "2") (pinfunction "2_2") (pintype "passive"))
      (node (ref "U4") (pin "3") (pinfunction "+_3") (pintype "bidirectional"))
    )
    (net (code "38") (name "Net-(U4A--)") (class "Default")
      (node (ref "R26") (pin "2") (pinfunction "2_2") (pintype "passive"))
      (node (ref "U4") (pin "2") (pinfunction "-_2") (pintype "bidirectional"))
      (node (ref "U5") (pin "8") (pinfunction "A_8") (pintype "bidirectional"))
    )
    (net (code "39") (name "Net-(U4A-OUT)") (class "Default")
      (node (ref "C30") (pin "1") (pinfunction "1_1") (pintype "passive"))
      (node (ref "U4") (pin "1") (pinfunction "OUT_1") (pintype "bidirectional"))
      (node (ref "U5") (pin "1") (pinfunction "W_1") (pintype "bidirectional"))
    )
    (net (code "40") (name "Net-(U4B-+)") (class "Default")
      (node (ref "C30") (pin "2") (pinfunction "2_2") (pintype "passive"))
      (node (ref "R27") (pin "2") (pinfunction "2_2") (pintype "passive"))
      (node (ref "R28") (pin "1") (pinfunction "1_1") (pintype "passive"))
      (node (ref "U4") (pin "5") (pinfunction "+_5") (pintype "bidirectional"))
    )
    (net (code "41") (name "Net-(U4B--)") (class "Default")
      (node (ref "R29") (pin "1") (pinfunction "1_1") (pintype "passive"))
      (node (ref "U4") (pin "6") (pinfunction "-_6") (pintype "bidirectional"))
      (node (ref "U4") (pin "7") (pinfunction "OUT_7") (pintype "bidirectional"))
    )
    (net (code "42") (name "Net-(U6-VIN)") (class "Default")
      (node (ref "C31") (pin "1") (pinfunction "1_1") (pintype "passive"))
      (node (ref "R29") (pin "2") (pinfunction "2_2") (pintype "passive"))
      (node (ref "U6") (pin "3") (pinfunction "VIN_3") (pintype "bidirectional"))
    )
    (net (code "43") (name "Net-(U7-BYP)") (class "Default")
      (node (ref "C39") (pin "2") (pinfunction "2_2") (pintype "passive"))
      (node (ref "U7") (pin "3") (pinfunction "BYP_3") (pintype "bidirectional"))
    )
    (net (code "44") (name "Net-(U7-SHDN#)") (class "Default")
      (node (ref "C35") (pin "1") (pinfunction "1_1") (pintype "passive"))
      (node (ref "CN2") (pin "2") (pinfunction "2_2") (pintype "bidirectional"))
      (node (ref "CN3") (pin "1") (pinfunction "1_1") (pintype "bidirectional"))
      (node (ref "U7") (pin "2") (pinfunction "VIN_2") (pintype "bidirectional"))
      (node (ref "U7") (pin "4") (pinfunction "SHDN#_4") (pintype "bidirectional"))
    )
    (net (code "45") (name "Net-(U8-BYP)") (class "Default")
      (node (ref "C40") (pin "2") (pinfunction "2_2") (pintype "passive"))
      (node (ref "U8") (pin "4") (pinfunction "BYP_4") (pintype "bidirectional"))
    )
    (net (code "46") (name "Net-(U8-SHDN#)") (class "Default")
      (node (ref "C37") (pin "1") (pinfunction "1_1") (pintype "passive"))
      (node (ref "C41") (pin "1") (pinfunction "1_1") (pintype "passive"))
      (node (ref "CN1") (pin "1") (pinfunction "1_1") (pintype "bidirectional"))
      (node (ref "CN3") (pin "3") (pinfunction "3_3") (pintype "bidirectional"))
      (node (ref "U8") (pin "1") (pinfunction "VIN_1") (pintype "bidirectional"))
      (node (ref "U8") (pin "3") (pinfunction "SHDN#_3") (pintype "bidirectional"))
      (node (ref "U9") (pin "1") (pinfunction "VIN_1") (pintype "bidirectional"))
      (node (ref "U9") (pin "3") (pinfunction "SHDN#_3") (pintype "bidirectional"))
    )
    (net (code "47") (name "Net-(U9-BYP)") (class "Default")
      (node (ref "C43") (pin "2") (pinfunction "2_2") (pintype "passive"))
      (node (ref "U9") (pin "4") (pinfunction "BYP_4") (pintype "bidirectional"))
    )
    (net (code "48") (name "Net-(U10-A2)") (class "Default")
      (node (ref "CN4") (pin "2") (pinfunction "2_2") (pintype "bidirectional"))
      (node (ref "U10") (pin "3") (pinfunction "A2_3") (pintype "bidirectional"))
    )
    (net (code "49") (name "Net-(U10-A3)") (class "Default")
      (node (ref "CN4") (pin "3") (pinfunction "3_3") (pintype "bidirectional"))
      (node (ref "U10") (pin "4") (pinfunction "A3_4") (pintype "bidirectional"))
    )
    (net (code "50") (name "Net-(U10-A4)") (class "Default")
      (node (ref "CN4") (pin "4") (pinfunction "4_4") (pintype "bidirectional"))
      (node (ref "U10") (pin "5") (pinfunction "A4_5") (pintype "bidirectional"))
    )
    (net (code "51") (name "Net-(U10-A5)") (class "Default")
      (node (ref "CN4") (pin "6") (pinfunction "6_6") (pintype "bidirectional"))
      (node (ref "U10") (pin "6") (pinfunction "A5_6") (pintype "bidirectional"))
    )
    (net (code "52") (name "Net-(U10-A6)") (class "Default")
      (node (ref "CN4") (pin "7") (pinfunction "7_7") (pintype "bidirectional"))
      (node (ref "U10") (pin "7") (pinfunction "A6_7") (pintype "bidirectional"))
    )
    (net (code "53") (name "Net-(U10-A7)") (class "Default")
      (node (ref "CN4") (pin "8") (pinfunction "8_8") (pintype "bidirectional"))
      (node (ref "U10") (pin "8") (pinfunction "A7_8") (pintype "bidirectional"))
    )
    (net (code "54") (name "unconnected-(U5-B-Pad7)") (class "Default")
      (node (ref "U5") (pin "7") (pinfunction "B_7") (pintype "bidirectional"))
    )
    (net (code "55") (name "unconnected-(U10-A1-Pad1)") (class "Default")
      (node (ref "U10") (pin "1") (pinfunction "A1_1") (pintype "bidirectional"))
    )
    (net (code "56") (name "unconnected-(U10-A8-Pad9)") (class "Default")
      (node (ref "U10") (pin "9") (pinfunction "A8_9") (pintype "bidirectional"))
    )
    (net (code "57") (name "unconnected-(U10-B1-Pad20)") (class "Default")
      (node (ref "U10") (pin "20") (pinfunction "B1_20") (pintype "bidirectional"))
    )
    (net (code "58") (name "unconnected-(U10-B8-Pad12)") (class "Default")
      (node (ref "U10") (pin "12") (pinfunction "B8_12") (pintype "bidirectional"))
    )
  )
)
